# Connectors.net
KiCad netlist of a schematic drawn in Altium Designer
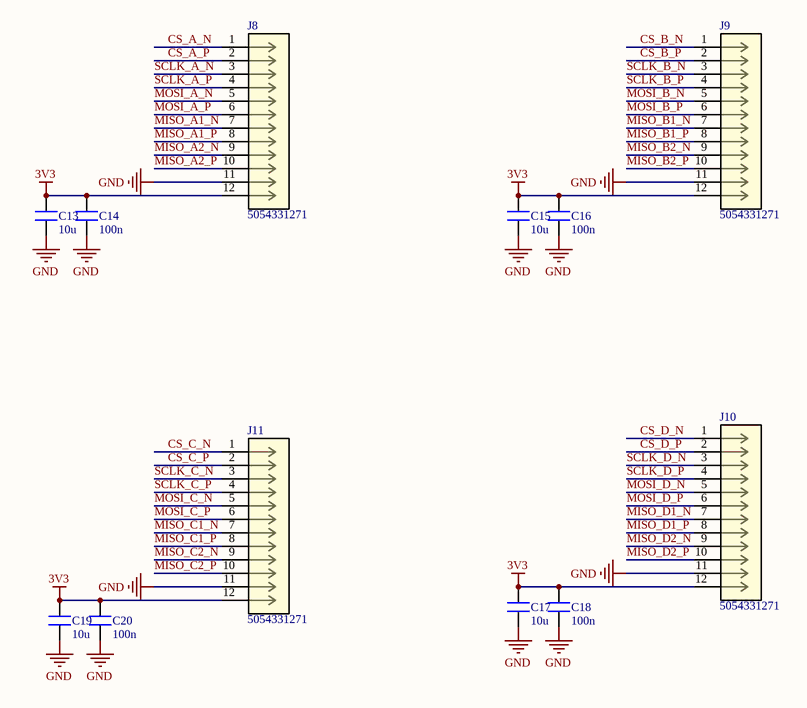
[diagram p0: Connectors.SchDoc]

(export (version "E")
  (design (tool "Eeschema 10.0.6"))
  (components
    (comp (ref "C13") (value "10u") (footprint "C 0603_L") (libsource (lib "ZYNQ_开发板") (part "C_1_8")))
    (comp (ref "C14") (value "100n") (footprint "C 0402_L") (libsource (lib "ZYNQ_开发板") (part "C_1")))
    (comp (ref "C15") (value "10u") (footprint "C 0603_L") (libsource (lib "ZYNQ_开发板") (part "C_1_8")))
    (comp (ref "C16") (value "100n") (footprint "C 0402_L") (libsource (lib "ZYNQ_开发板") (part "C_1")))
    (comp (ref "C17") (value "10u") (footprint "C 0603_L") (libsource (lib "ZYNQ_开发板") (part "C_1_8")))
    (comp (ref "C18") (value "100n") (footprint "C 0402_L") (libsource (lib "ZYNQ_开发板") (part "C_1")))
    (comp (ref "C19") (value "10u") (footprint "C 0603_L") (libsource (lib "ZYNQ_开发板") (part "C_1_8")))
    (comp (ref "C20") (value "100n") (footprint "C 0402_L") (libsource (lib "ZYNQ_开发板") (part "C_1")))
    (comp (ref "J8")
      (value "5054331271")
      (footprint "CONN_505433_12_MOL")
      (fields (field (name "COPYRIGHT") "Copyright (C) 2025 Ultra Librarian. All rights reserved."))
      (libsource (lib "5054331271") (part "5054331271"))
    )
    (comp (ref "J9")
      (value "5054331271")
      (footprint "CONN_505433_12_MOL")
      (fields (field (name "COPYRIGHT") "Copyright (C) 2025 Ultra Librarian. All rights reserved."))
      (libsource (lib "5054331271") (part "5054331271"))
    )
    (comp (ref "J10")
      (value "5054331271")
      (footprint "CONN_505433_12_MOL")
      (fields (field (name "COPYRIGHT") "Copyright (C) 2025 Ultra Librarian. All rights reserved."))
      (libsource (lib "5054331271") (part "5054331271"))
    )
    (comp (ref "J11")
      (value "5054331271")
      (footprint "CONN_505433_12_MOL")
      (fields (field (name "COPYRIGHT") "Copyright (C) 2025 Ultra Librarian. All rights reserved."))
      (libsource (lib "5054331271") (part "5054331271"))
    )
  )
  (nets
    (net (code "1") (name "/CS_A_N") (class "Default")
      (node (ref "J8") (pin "1") (pinfunction "1_1") (pintype "passive"))
    )
    (net (code "2") (name "/CS_A_P") (class "Default")
      (node (ref "J8") (pin "2") (pinfunction "2_2") (pintype "passive"))
    )
    (net (code "3") (name "/CS_B_N") (class "Default")
      (node (ref "J9") (pin "1") (pinfunction "1_1") (pintype "passive"))
    )
    (net (code "4") (name "/CS_B_P") (class "Default")
      (node (ref "J9") (pin "2") (pinfunction "2_2") (pintype "passive"))
    )
    (net (code "5") (name "/CS_C_N") (class "Default")
      (node (ref "J11") (pin "1") (pinfunction "1_1") (pintype "passive"))
    )
    (net (code "6") (name "/CS_C_P") (class "Default")
      (node (ref "J11") (pin "2") (pinfunction "2_2") (pintype "passive"))
    )
    (net (code "7") (name "/CS_D_N") (class "Default")
      (node (ref "J10") (pin "1") (pinfunction "1_1") (pintype "passive"))
    )
    (net (code "8") (name "/CS_D_P") (class "Default")
      (node (ref "J10") (pin "2") (pinfunction "2_2") (pintype "passive"))
    )
    (net (code "9") (name "/MISO_A1_N") (class "Default")
      (node (ref "J8") (pin "7") (pinfunction "7_7") (pintype "passive"))
    )
    (net (code "10") (name "/MISO_A1_P") (class "Default")
      (node (ref "J8") (pin "8") (pinfunction "8_8") (pintype "passive"))
    )
    (net (code "11") (name "/MISO_A2_N") (class "Default")
      (node (ref "J8") (pin "9") (pinfunction "9_9") (pintype "passive"))
    )
    (net (code "12") (name "/MISO_A2_P") (class "Default")
      (node (ref "J8") (pin "10") (pinfunction "10_10") (pintype "passive"))
    )
    (net (code "13") (name "/MISO_B1_N") (class "Default")
      (node (ref "J9") (pin "7") (pinfunction "7_7") (pintype "passive"))
    )
    (net (code "14") (name "/MISO_B1_P") (class "Default")
      (node (ref "J9") (pin "8") (pinfunction "8_8") (pintype "passive"))
    )
    (net (code "15") (name "/MISO_B2_N") (class "Default")
      (node (ref "J9") (pin "9") (pinfunction "9_9") (pintype "passive"))
    )
    (net (code "16") (name "/MISO_B2_P") (class "Default")
      (node (ref "J9") (pin "10") (pinfunction "10_10") (pintype "passive"))
    )
    (net (code "17") (name "/MISO_C1_N") (class "Default")
      (node (ref "J11") (pin "7") (pinfunction "7_7") (pintype "passive"))
    )
    (net (code "18") (name "/MISO_C1_P") (class "Default")
      (node (ref "J11") (pin "8") (pinfunction "8_8") (pintype "passive"))
    )
    (net (code "19") (name "/MISO_C2_N") (class "Default")
      (node (ref "J11") (pin "9") (pinfunction "9_9") (pintype "passive"))
    )
    (net (code "20") (name "/MISO_C2_P") (class "Default")
      (node (ref "J11") (pin "10") (pinfunction "10_10") (pintype "passive"))
    )
    (net (code "21") (name "/MISO_D1_N") (class "Default")
      (node (ref "J10") (pin "7") (pinfunction "7_7") (pintype "passive"))
    )
    (net (code "22") (name "/MISO_D1_P") (class "Default")
      (node (ref "J10") (pin "8") (pinfunction "8_8") (pintype "passive"))
    )
    (net (code "23") (name "/MISO_D2_N") (class "Default")
      (node (ref "J10") (pin "9") (pinfunction "9_9") (pintype "passive"))
    )
    (net (code "24") (name "/MISO_D2_P") (class "Default")
      (node (ref "J10") (pin "10") (pinfunction "10_10") (pintype "passive"))
    )
    (net (code "25") (name "/MOSI_A_N") (class "Default")
      (node (ref "J8") (pin "5") (pinfunction "5_5") (pintype "passive"))
    )
    (net (code "26") (name "/MOSI_A_P") (class "Default")
      (node (ref "J8") (pin "6") (pinfunction "6_6") (pintype "passive"))
    )
    (net (code "27") (name "/MOSI_B_N") (class "Default")
      (node (ref "J9") (pin "5") (pinfunction "5_5") (pintype "passive"))
    )
    (net (code "28") (name "/MOSI_B_P") (class "Default")
      (node (ref "J9") (pin "6") (pinfunction "6_6") (pintype "passive"))
    )
    (net (code "29") (name "/MOSI_C_N") (class "Default")
      (node (ref "J11") (pin "5") (pinfunction "5_5") (pintype "passive"))
    )
    (net (code "30") (name "/MOSI_C_P") (class "Default")
      (node (ref "J11") (pin "6") (pinfunction "6_6") (pintype "passive"))
    )
    (net (code "31") (name "/MOSI_D_N") (class "Default")
      (node (ref "J10") (pin "5") (pinfunction "5_5") (pintype "passive"))
    )
    (net (code "32") (name "/MOSI_D_P") (class "Default")
      (node (ref "J10") (pin "6") (pinfunction "6_6") (pintype "passive"))
    )
    (net (code "33") (name "/SCLK_A_N") (class "Default")
      (node (ref "J8") (pin "3") (pinfunction "3_3") (pintype "passive"))
    )
    (net (code "34") (name "/SCLK_A_P") (class "Default")
      (node (ref "J8") (pin "4") (pinfunction "4_4") (pintype "passive"))
    )
    (net (code "35") (name "/SCLK_B_N") (class "Default")
      (node (ref "J9") (pin "3") (pinfunction "3_3") (pintype "passive"))
    )
    (net (code "36") (name "/SCLK_B_P") (class "Default")
      (node (ref "J9") (pin "4") (pinfunction "4_4") (pintype "passive"))
    )
    (net (code "37") (name "/SCLK_C_N") (class "Default")
      (node (ref "J11") (pin "3") (pinfunction "3_3") (pintype "passive"))
    )
    (net (code "38") (name "/SCLK_C_P") (class "Default")
      (node (ref "J11") (pin "4") (pinfunction "4_4") (pintype "passive"))
    )
    (net (code "39") (name "/SCLK_D_N") (class "Default")
      (node (ref "J10") (pin "3") (pinfunction "3_3") (pintype "passive"))
    )
    (net (code "40") (name "/SCLK_D_P") (class "Default")
      (node (ref "J10") (pin "4") (pinfunction "4_4") (pintype "passive"))
    )
    (net (code "41") (name "3V3") (class "Default")
      (node (ref "C13") (pin "2") (pintype "passive"))
      (node (ref "C14") (pin "2") (pintype "passive"))
      (node (ref "C15") (pin "2") (pintype "passive"))
      (node (ref "C16") (pin "2") (pintype "passive"))
      (node (ref "C17") (pin "2") (pintype "passive"))
      (node (ref "C18") (pin "2") (pintype "passive"))
      (node (ref "C19") (pin "2") (pintype "passive"))
      (node (ref "C20") (pin "2") (pintype "passive"))
      (node (ref "J10") (pin "12") (pinfunction "12_12") (pintype "passive"))
      (node (ref "J11") (pin "12") (pinfunction "12_12") (pintype "passive"))
      (node (ref "J8") (pin "12") (pinfunction "12_12") (pintype "passive"))
      (node (ref "J9") (pin "12") (pinfunction "12_12") (pintype "passive"))
    )
    (net (code "42") (name "GND") (class "Default")
      (node (ref "C13") (pin "1") (pintype "passive"))
      (node (ref "C14") (pin "1") (pintype "passive"))
      (node (ref "C15") (pin "1") (pintype "passive"))
      (node (ref "C16") (pin "1") (pintype "passive"))
      (node (ref "C17") (pin "1") (pintype "passive"))
      (node (ref "C18") (pin "1") (pintype "passive"))
      (node (ref "C19") (pin "1") (pintype "passive"))
      (node (ref "C20") (pin "1") (pintype "passive"))
      (node (ref "J10") (pin "11") (pinfunction "11_11") (pintype "passive"))
      (node (ref "J11") (pin "11") (pinfunction "11_11") (pintype "passive"))
      (node (ref "J8") (pin "11") (pinfunction "11_11") (pintype "passive"))
      (node (ref "J9") (pin "11") (pinfunction "11_11") (pintype "passive"))
    )
  )
)
